# MCU_Power.net
KiCad netlist of a schematic drawn in Altium Designer
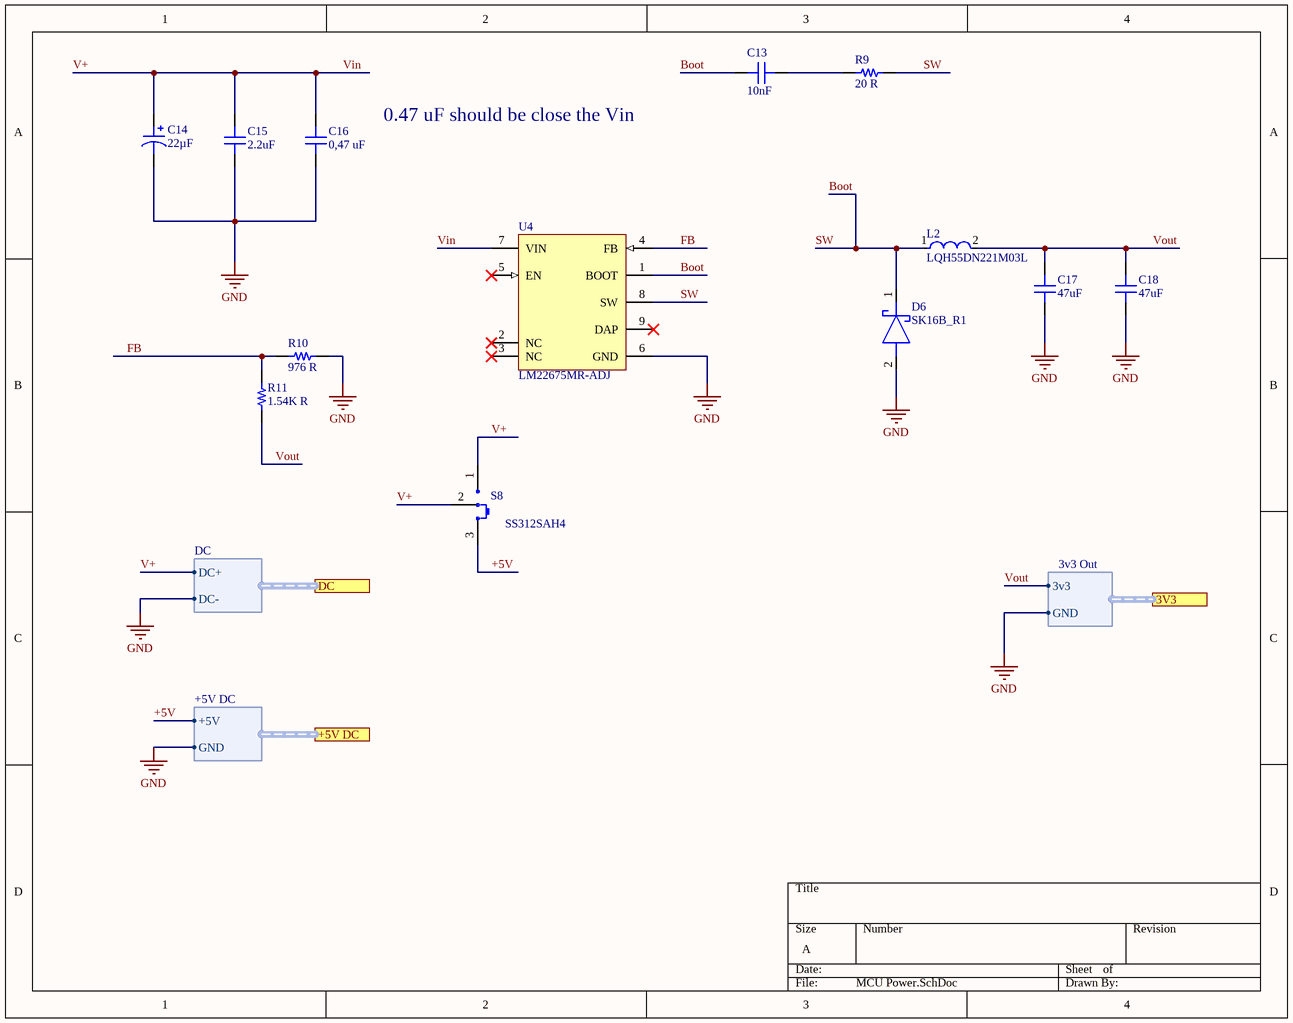
[diagram p0: MCU Power.SchDoc]

(export (version "E")
  (design (tool "Eeschema 10.0.6"))
  (components
    (comp (ref "C13")
      (value "10nF")
      (footprint "CAP 0603_1608")
      (description "CAP CER 100PF 50V C0G/NP0 0603")
      (fields (field (name "PART NUMBER") "C0603X101F5GACAUTO") (field (name "MANUFACTURER") "KEMET"))
      (libsource (lib "Celestial Altium Library - altium_library (2)") (part "Capacitor"))
    )
    (comp (ref "C14")
      (value "22µF")
      (footprint "CAP TH ALUM ELEC D12.50mm S5.00mm H27.00mm")
      (description "CAP ALUM 22UF 20% 350V RADIAL")
      (fields (field (name "PART NUMBER") "UVZ2V220MHD") (field (name "MANUFACTURER") "Nichicon"))
      (libsource (lib "Celestial Altium Library - altium_library (2)") (part "Polarised Capacitor"))
    )
    (comp (ref "C15")
      (value "2.2uF")
      (footprint "CAP 0805_2012")
      (description "CAP CER 33PF 250V C0G/NP0 0805")
      (fields (field (name "PART NUMBER") "CBR08C330JAGAC") (field (name "MANUFACTURER") "KEMET"))
      (libsource (lib "Celestial Altium Library - altium_library (2)") (part "Capacitor"))
    )
    (comp (ref "C16")
      (value "0,47 uF")
      (footprint "CAP 0603_1608")
      (description "CAP CER 100PF 50V C0G/NP0 0603")
      (fields (field (name "PART NUMBER") "C0603X101F5GACAUTO") (field (name "MANUFACTURER") "KEMET"))
      (libsource (lib "Celestial Altium Library - altium_library (2)") (part "Capacitor"))
    )
    (comp (ref "C17")
      (value "47uF")
      (footprint "CAP 0805_2012")
      (description "CAP CER 33PF 250V C0G/NP0 0805")
      (fields (field (name "PART NUMBER") "CBR08C330JAGAC") (field (name "MANUFACTURER") "KEMET"))
      (libsource (lib "Celestial Altium Library - altium_library (2)") (part "Capacitor"))
    )
    (comp (ref "C18")
      (value "47uF")
      (footprint "CAP 0805_2012")
      (description "CAP CER 33PF 250V C0G/NP0 0805")
      (fields (field (name "PART NUMBER") "CBR08C330JAGAC") (field (name "MANUFACTURER") "KEMET"))
      (libsource (lib "Celestial Altium Library - altium_library (2)") (part "Capacitor"))
    )
    (comp (ref "D6")
      (value "SK16B_R1")
      (footprint "SamacSys:DIONM5236X261N")
      (description "Schottky Diode")
      (fields
        (field (name "MANUFACTURER_PART_NUMBER") "SK16B R4")
        (field (name "MOUSER PART NUMBER") "821-SK16BR4")
      )
      (libsource (lib "*") (part "SK16B_R4"))
    )
    (comp (ref "L2")
      (value "LQH55DN221M03L")
      (footprint "FP-LQH55DN_03-MFG(100uH)")
      (description "Wire Wound Ferrite Inductor for Power Lines 220μH ±20% 3.36Ω  0.32A 2220")
      (fields (field (name "TOLERANCE") "20%"))
      (libsource (lib "Schlib1") (part "CMP-06042-002541-1"))
    )
    (comp (ref "R9")
      (value "20 R")
      (footprint "RES 0603_1608")
      (description "10-50 ohm")
      (fields
        (field (name "PART NUMBER") "RNCS0603BKE10K0")
        (field (name "MANUFACTURER") "Stackpole Electronics Inc")
      )
      (libsource (lib "Celestial Altium Library - altium_library (2)") (part "Resistor"))
    )
    (comp (ref "R10")
      (value "976 R")
      (footprint "RES 0603_1608")
      (description "RES 10K OHM 0.1% 1/16W 0603")
      (fields
        (field (name "PART NUMBER") "RNCS0603BKE10K0")
        (field (name "MANUFACTURER") "Stackpole Electronics Inc")
      )
      (libsource (lib "Celestial Altium Library - altium_library (2)") (part "Resistor"))
    )
    (comp (ref "R11")
      (value "1.54K R")
      (footprint "RES 0603_1608")
      (description "RES 10K OHM 0.1% 1/16W 0603")
      (fields
        (field (name "PART NUMBER") "RNCS0603BKE10K0")
        (field (name "MANUFACTURER") "Stackpole Electronics Inc")
      )
      (libsource (lib "Celestial Altium Library - altium_library (2)") (part "Resistor"))
    )
    (comp (ref "S8")
      (value "SS312SAH4")
      (footprint "NKK SS312SAH4")
      (description "SWITCH SLIDE SPDT 0.4VA 28V")
      (fields (field (name "MANUFACTURER") "NKK Switches"))
      (libsource (lib "Celestial Altium Library - altium_library (2)") (part "NKK SS312"))
    )
    (comp (ref "U4")
      (value "LM22675MR-ADJ")
      (footprint "MRA08B_M")
      (description "1A SIMPLE SWITCHER® Step-Down Voltage Regulator with Precision Enable, 8-pin PSOP")
      (fields (field (name "MANUFACTURER") "National Semiconductor"))
      (libsource (lib "Altium Content Vault") (part "PM-REG-LM22675MR"))
    )
  )
  (nets
    (net (code "4") (name "/+5V") (class "Default")
      (node (ref "S8") (pin "3") (pinfunction "3_3") (pintype "passive"))
    )
    (net (code "5") (name "/Boot") (class "Default")
      (node (ref "C13") (pin "2") (pinfunction "2_2") (pintype "passive"))
      (node (ref "D6") (pin "1") (pinfunction "K_1") (pintype "passive"))
      (node (ref "L2") (pin "1") (pinfunction "1_1") (pintype "passive"))
      (node (ref "R9") (pin "1") (pinfunction "1_1") (pintype "passive"))
      (node (ref "U4") (pin "1") (pinfunction "BOOT_1") (pintype "passive"))
      (node (ref "U4") (pin "8") (pinfunction "SW_8") (pintype "power_in"))
    )
    (net (code "6") (name "/FB") (class "Default")
      (node (ref "R10") (pin "2") (pinfunction "2_2") (pintype "passive"))
      (node (ref "R11") (pin "2") (pinfunction "2_2") (pintype "passive"))
      (node (ref "U4") (pin "4") (pinfunction "FB_4") (pintype "input"))
    )
    (net (code "7") (name "/V+") (class "Default")
      (node (ref "C14") (pin "1") (pinfunction "1_1") (pintype "passive"))
      (node (ref "C15") (pin "2") (pinfunction "2_2") (pintype "passive"))
      (node (ref "C16") (pin "2") (pinfunction "2_2") (pintype "passive"))
      (node (ref "S8") (pin "1") (pinfunction "1_1") (pintype "passive"))
      (node (ref "S8") (pin "2") (pinfunction "COM_2") (pintype "passive"))
      (node (ref "U4") (pin "7") (pinfunction "VIN_7") (pintype "power_in"))
    )
    (net (code "8") (name "/Vout") (class "Default")
      (node (ref "C17") (pin "2") (pinfunction "2_2") (pintype "passive"))
      (node (ref "C18") (pin "2") (pinfunction "2_2") (pintype "passive"))
      (node (ref "L2") (pin "2") (pinfunction "2_2") (pintype "passive"))
      (node (ref "R11") (pin "1") (pinfunction "1_1") (pintype "passive"))
    )
    (net (code "12") (name "GND") (class "Default")
      (node (ref "C14") (pin "2") (pinfunction "2_2") (pintype "passive"))
      (node (ref "C15") (pin "1") (pinfunction "1_1") (pintype "passive"))
      (node (ref "C16") (pin "1") (pinfunction "1_1") (pintype "passive"))
      (node (ref "C17") (pin "1") (pinfunction "1_1") (pintype "passive"))
      (node (ref "C18") (pin "1") (pinfunction "1_1") (pintype "passive"))
      (node (ref "D6") (pin "2") (pinfunction "A_2") (pintype "passive"))
      (node (ref "R10") (pin "1") (pinfunction "1_1") (pintype "passive"))
      (node (ref "U4") (pin "6") (pinfunction "GND_6") (pintype "power_in"))
    )
    (net (code "13") (name "Net-(C13-Pad1)") (class "Default")
      (node (ref "C13") (pin "1") (pinfunction "1_1") (pintype "passive"))
      (node (ref "R9") (pin "2") (pinfunction "2_2") (pintype "passive"))
    )
    (net (code "14") (name "unconnected-(U4-DAP-Pad9)") (class "Default")
      (node (ref "U4") (pin "9") (pinfunction "DAP_9") (pintype "power_in+no_connect"))
    )
    (net (code "15") (name "unconnected-(U4-EN-Pad5)") (class "Default")
      (node (ref "U4") (pin "5") (pinfunction "EN_5") (pintype "input+no_connect"))
    )
    (net (code "16") (name "unconnected-(U4-NC-Pad2)") (class "Default")
      (node (ref "U4") (pin "2") (pinfunction "NC_2") (pintype "passive+no_connect"))
    )
    (net (code "17") (name "unconnected-(U4-NC-Pad3)") (class "Default")
      (node (ref "U4") (pin "3") (pinfunction "NC_3") (pintype "passive+no_connect"))
    )
  )
)
